# fpc-30-lcd_ERM12864-6.net
KiCad netlist of a schematic drawn in EAGLE
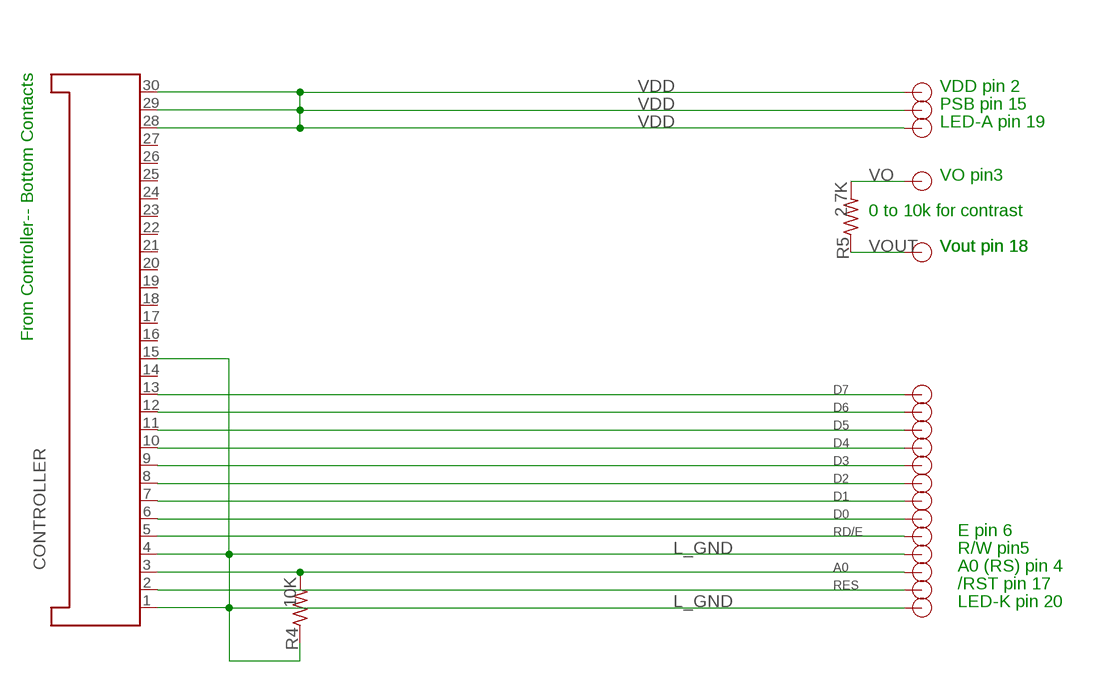
[diagram p0: schematic, sheet 1]

(export (version "E")
  (design (tool "Eeschema 10.0.6"))
  (components
    (comp (ref "/RST")
      (value "TP-1")
      (footprint "eagle-import:TP")
      (libsource (lib "eagle-import") (part "TP-1"))
    )
    (comp (ref "A0/RS")
      (value "TP-1")
      (footprint "eagle-import:TP")
      (libsource (lib "eagle-import") (part "TP-1"))
    )
    (comp (ref "CONTROLLER")
      (value "FPC30-Top_pins")
      (footprint "eagle-import:FH12-30S-0.5SH")
      (libsource (lib "eagle-import") (part "FPC_30-PINS"))
    )
    (comp (ref "D0")
      (value "D7")
      (footprint "eagle-import:TP")
      (libsource (lib "eagle-import") (part "TP-1"))
    )
    (comp (ref "D1")
      (value "TP-1")
      (footprint "eagle-import:TP")
      (libsource (lib "eagle-import") (part "TP-1"))
    )
    (comp (ref "D2")
      (value "TP-1")
      (footprint "eagle-import:TP")
      (libsource (lib "eagle-import") (part "TP-1"))
    )
    (comp (ref "D3")
      (value "TP-1")
      (footprint "eagle-import:TP")
      (libsource (lib "eagle-import") (part "TP-1"))
    )
    (comp (ref "D4")
      (value "TP-1")
      (footprint "eagle-import:TP")
      (libsource (lib "eagle-import") (part "TP-1"))
    )
    (comp (ref "D5")
      (value "TP-1")
      (footprint "eagle-import:TP")
      (libsource (lib "eagle-import") (part "TP-1"))
    )
    (comp (ref "D6")
      (value "TP-1")
      (footprint "eagle-import:TP")
      (libsource (lib "eagle-import") (part "TP-1"))
    )
    (comp (ref "D7")
      (value "D7")
      (footprint "eagle-import:TP")
      (libsource (lib "eagle-import") (part "TP-1"))
    )
    (comp (ref "LED_A")
      (value "TP-1")
      (footprint "eagle-import:TP")
      (libsource (lib "eagle-import") (part "TP-1"))
    )
    (comp (ref "LED_K")
      (value "TP-1")
      (footprint "eagle-import:TP")
      (libsource (lib "eagle-import") (part "TP-1"))
    )
    (comp (ref "PSB")
      (value "TP-1")
      (footprint "eagle-import:TP")
      (libsource (lib "eagle-import") (part "TP-1"))
    )
    (comp (ref "R/W")
      (value "TP-1")
      (footprint "eagle-import:TP")
      (libsource (lib "eagle-import") (part "TP-1"))
    )
    (comp (ref "R4")
      (value "10K")
      (footprint "eagle-import:R0603")
      (libsource (lib "eagle-import") (part "R-US_R0603"))
    )
    (comp (ref "R5")
      (value "2.7K")
      (footprint "eagle-import:R0603")
      (libsource (lib "eagle-import") (part "R-US_R0603"))
    )
    (comp (ref "RD/E")
      (value "TP-1")
      (footprint "eagle-import:TP")
      (libsource (lib "eagle-import") (part "TP-1"))
    )
    (comp (ref "VDD")
      (value "TP-1")
      (footprint "eagle-import:TP")
      (libsource (lib "eagle-import") (part "TP-1"))
    )
    (comp (ref "VO")
      (value "D7")
      (footprint "eagle-import:TP")
      (libsource (lib "eagle-import") (part "TP-1"))
    )
    (comp (ref "VOUT")
      (value "D7")
      (footprint "eagle-import:TP")
      (libsource (lib "eagle-import") (part "TP-1"))
    )
  )
  (nets
    (net (code "1") (name "/A0") (class "Default")
      (node (ref "A0/RS") (pin "P$1") (pinfunction "P$1_P$1") (pintype "bidirectional"))
      (node (ref "CONTROLLER") (pin "3") (pinfunction "P$3_3") (pintype "bidirectional"))
      (node (ref "R4") (pin "2") (pinfunction "2_2") (pintype "passive"))
    )
    (net (code "2") (name "/D0") (class "Default")
      (node (ref "CONTROLLER") (pin "6") (pinfunction "P$6_6") (pintype "bidirectional"))
      (node (ref "D0") (pin "P$1") (pinfunction "P$1_P$1") (pintype "bidirectional"))
    )
    (net (code "3") (name "/D1") (class "Default")
      (node (ref "CONTROLLER") (pin "7") (pinfunction "P$7_7") (pintype "bidirectional"))
      (node (ref "D1") (pin "P$1") (pinfunction "P$1_P$1") (pintype "bidirectional"))
    )
    (net (code "4") (name "/D2") (class "Default")
      (node (ref "CONTROLLER") (pin "8") (pinfunction "P$8_8") (pintype "bidirectional"))
      (node (ref "D2") (pin "P$1") (pinfunction "P$1_P$1") (pintype "bidirectional"))
    )
    (net (code "5") (name "/D3") (class "Default")
      (node (ref "CONTROLLER") (pin "9") (pinfunction "P$9_9") (pintype "bidirectional"))
      (node (ref "D3") (pin "P$1") (pinfunction "P$1_P$1") (pintype "bidirectional"))
    )
    (net (code "6") (name "/D4") (class "Default")
      (node (ref "CONTROLLER") (pin "10") (pinfunction "P$10_10") (pintype "bidirectional"))
      (node (ref "D4") (pin "P$1") (pinfunction "P$1_P$1") (pintype "bidirectional"))
    )
    (net (code "7") (name "/D5") (class "Default")
      (node (ref "CONTROLLER") (pin "11") (pinfunction "P$11_11") (pintype "bidirectional"))
      (node (ref "D5") (pin "P$1") (pinfunction "P$1_P$1") (pintype "bidirectional"))
    )
    (net (code "8") (name "/D6") (class "Default")
      (node (ref "CONTROLLER") (pin "12") (pinfunction "P$12_12") (pintype "bidirectional"))
      (node (ref "D6") (pin "P$1") (pinfunction "P$1_P$1") (pintype "bidirectional"))
    )
    (net (code "9") (name "/D7") (class "Default")
      (node (ref "CONTROLLER") (pin "13") (pinfunction "P$13_13") (pintype "bidirectional"))
      (node (ref "D7") (pin "P$1") (pinfunction "P$1_P$1") (pintype "bidirectional"))
    )
    (net (code "10") (name "/L_GND") (class "Default")
      (node (ref "CONTROLLER") (pin "1") (pinfunction "P$1_1") (pintype "bidirectional"))
      (node (ref "CONTROLLER") (pin "15") (pinfunction "P$15_15") (pintype "bidirectional"))
      (node (ref "CONTROLLER") (pin "4") (pinfunction "P$4_4") (pintype "bidirectional"))
      (node (ref "LED_K") (pin "P$1") (pinfunction "P$1_P$1") (pintype "bidirectional"))
      (node (ref "R/W") (pin "P$1") (pinfunction "P$1_P$1") (pintype "bidirectional"))
      (node (ref "R4") (pin "1") (pinfunction "1_1") (pintype "passive"))
    )
    (net (code "11") (name "/RD{slash}E") (class "Default")
      (node (ref "CONTROLLER") (pin "5") (pinfunction "P$5_5") (pintype "bidirectional"))
      (node (ref "RD/E") (pin "P$1") (pinfunction "P$1_P$1") (pintype "bidirectional"))
    )
    (net (code "12") (name "/RES") (class "Default")
      (node (ref "/RST") (pin "P$1") (pinfunction "P$1_P$1") (pintype "bidirectional"))
      (node (ref "CONTROLLER") (pin "2") (pinfunction "P$2_2") (pintype "bidirectional"))
    )
    (net (code "13") (name "/VDD") (class "Default")
      (node (ref "CONTROLLER") (pin "28") (pinfunction "P$28_28") (pintype "bidirectional"))
      (node (ref "CONTROLLER") (pin "29") (pinfunction "P$29_29") (pintype "bidirectional"))
      (node (ref "CONTROLLER") (pin "30") (pinfunction "P$30_30") (pintype "bidirectional"))
      (node (ref "LED_A") (pin "P$1") (pinfunction "P$1_P$1") (pintype "bidirectional"))
      (node (ref "PSB") (pin "P$1") (pinfunction "P$1_P$1") (pintype "bidirectional"))
      (node (ref "VDD") (pin "P$1") (pinfunction "P$1_P$1") (pintype "bidirectional"))
    )
    (net (code "14") (name "/VO") (class "Default")
      (node (ref "R5") (pin "2") (pinfunction "2_2") (pintype "passive"))
      (node (ref "VO") (pin "P$1") (pinfunction "P$1_P$1") (pintype "bidirectional"))
    )
    (net (code "15") (name "/VOUT") (class "Default")
      (node (ref "R5") (pin "1") (pinfunction "1_1") (pintype "passive"))
      (node (ref "VOUT") (pin "P$1") (pinfunction "P$1_P$1") (pintype "bidirectional"))
    )
    (net (code "16") (name "unconnected-(CONTROLLER-P$14-Pad14)") (class "Default")
      (node (ref "CONTROLLER") (pin "14") (pinfunction "P$14_14") (pintype "bidirectional"))
    )
    (net (code "17") (name "unconnected-(CONTROLLER-P$16-Pad16)") (class "Default")
      (node (ref "CONTROLLER") (pin "16") (pinfunction "P$16_16") (pintype "bidirectional"))
    )
    (net (code "18") (name "unconnected-(CONTROLLER-P$17-Pad17)") (class "Default")
      (node (ref "CONTROLLER") (pin "17") (pinfunction "P$17_17") (pintype "bidirectional"))
    )
    (net (code "19") (name "unconnected-(CONTROLLER-P$18-Pad18)") (class "Default")
      (node (ref "CONTROLLER") (pin "18") (pinfunction "P$18_18") (pintype "bidirectional"))
    )
    (net (code "20") (name "unconnected-(CONTROLLER-P$19-Pad19)") (class "Default")
      (node (ref "CONTROLLER") (pin "19") (pinfunction "P$19_19") (pintype "bidirectional"))
    )
    (net (code "21") (name "unconnected-(CONTROLLER-P$20-Pad20)") (class "Default")
      (node (ref "CONTROLLER") (pin "20") (pinfunction "P$20_20") (pintype "bidirectional"))
    )
    (net (code "22") (name "unconnected-(CONTROLLER-P$21-Pad21)") (class "Default")
      (node (ref "CONTROLLER") (pin "21") (pinfunction "P$21_21") (pintype "bidirectional"))
    )
    (net (code "23") (name "unconnected-(CONTROLLER-P$22-Pad22)") (class "Default")
      (node (ref "CONTROLLER") (pin "22") (pinfunction "P$22_22") (pintype "bidirectional"))
    )
    (net (code "24") (name "unconnected-(CONTROLLER-P$23-Pad23)") (class "Default")
      (node (ref "CONTROLLER") (pin "23") (pinfunction "P$23_23") (pintype "bidirectional"))
    )
    (net (code "25") (name "unconnected-(CONTROLLER-P$24-Pad24)") (class "Default")
      (node (ref "CONTROLLER") (pin "24") (pinfunction "P$24_24") (pintype "bidirectional"))
    )
    (net (code "26") (name "unconnected-(CONTROLLER-P$25-Pad25)") (class "Default")
      (node (ref "CONTROLLER") (pin "25") (pinfunction "P$25_25") (pintype "bidirectional"))
    )
    (net (code "27") (name "unconnected-(CONTROLLER-P$26-Pad26)") (class "Default")
      (node (ref "CONTROLLER") (pin "26") (pinfunction "P$26_26") (pintype "bidirectional"))
    )
    (net (code "28") (name "unconnected-(CONTROLLER-P$27-Pad27)") (class "Default")
      (node (ref "CONTROLLER") (pin "27") (pinfunction "P$27_27") (pintype "bidirectional"))
    )
  )
)
